# dual_encoder_shield_5v_revb.net
KiCad netlist of a schematic drawn in EAGLE
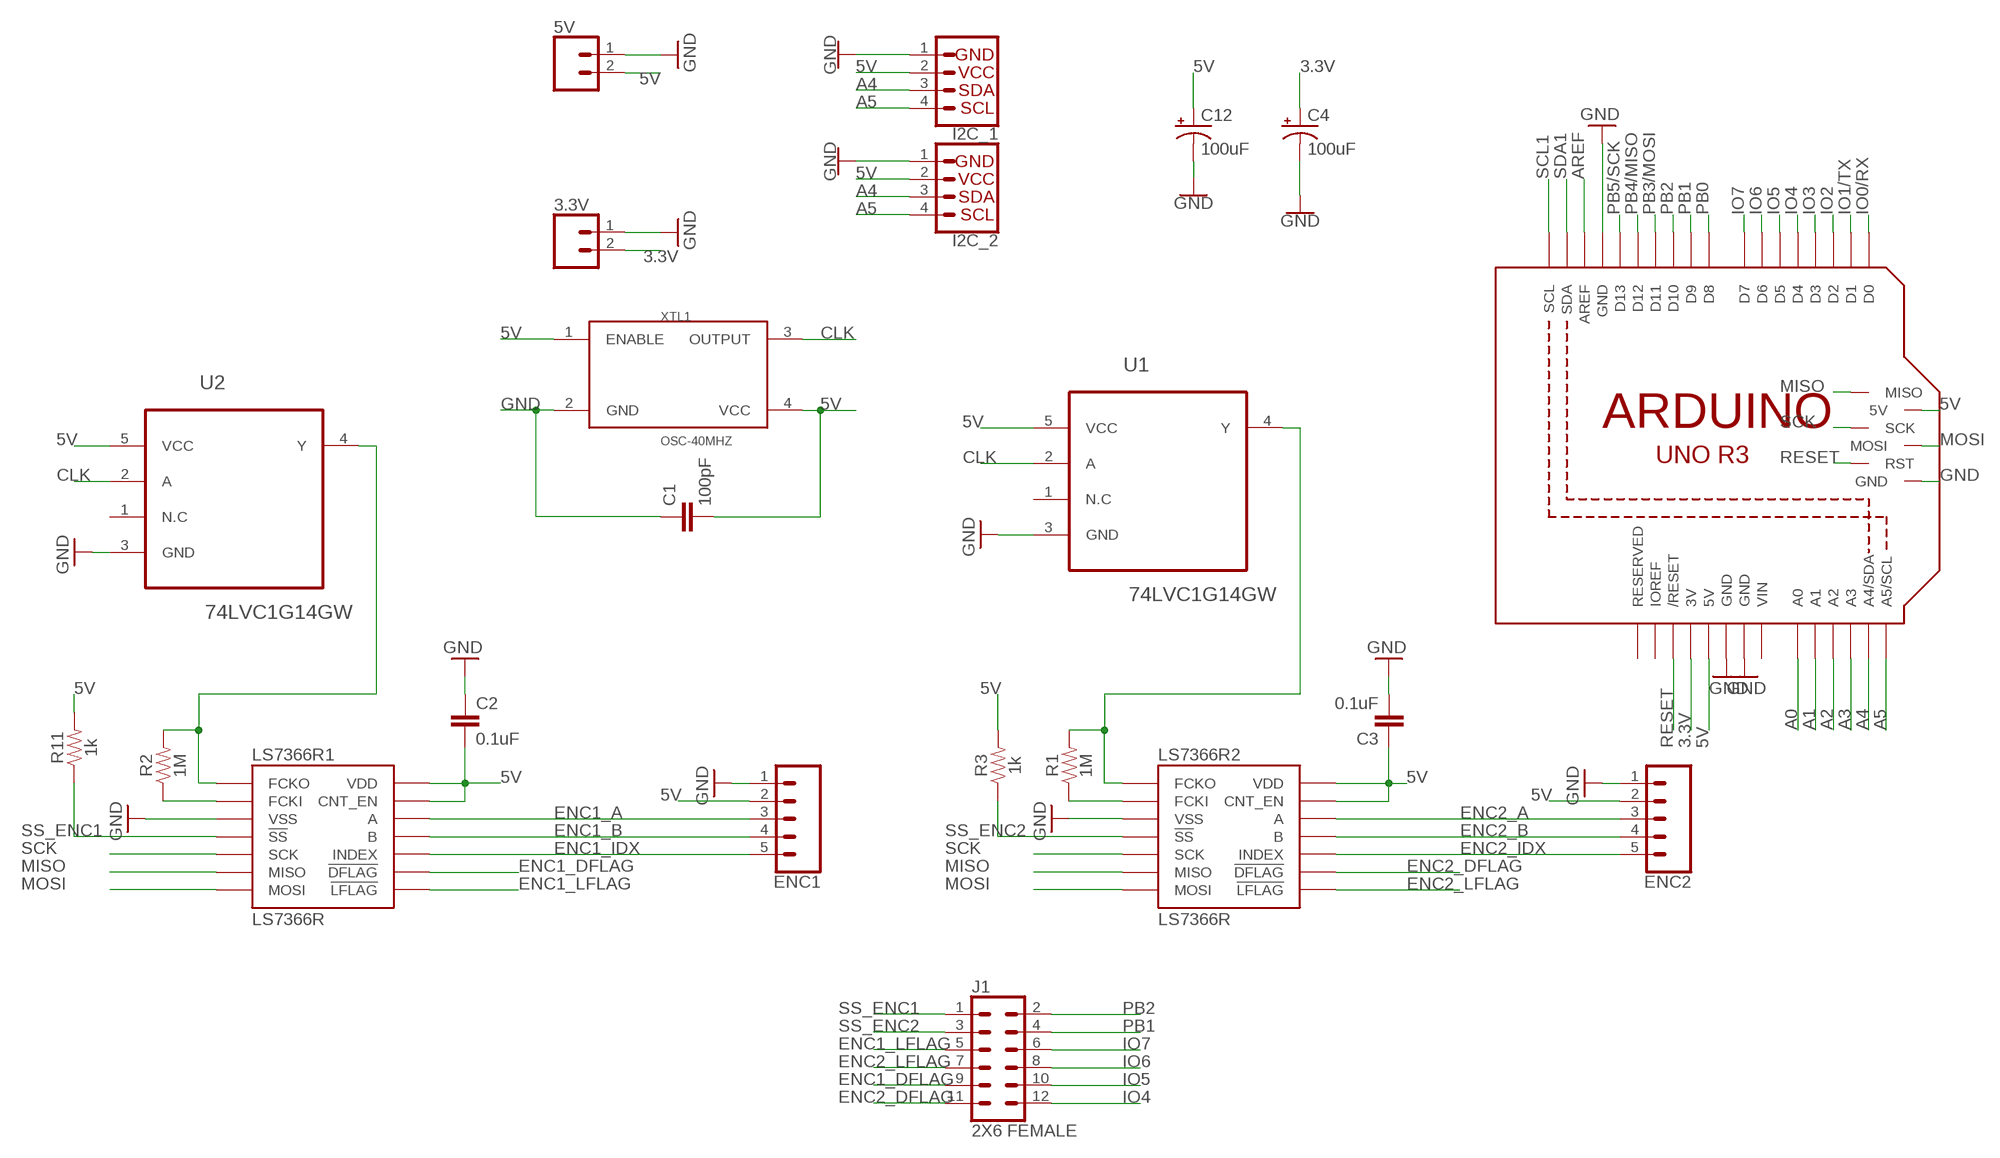
[diagram p0: schematic, sheet 1]

(export (version "E")
  (design (tool "Eeschema 10.0.6"))
  (components
    (comp (ref "3.3V")
      (value "CONN_02-JST-2MM-SMT")
      (footprint "eagle-import:JST-2-SMD")
      (libsource (lib "eagle-import") (part "CONN_02-JST-2MM-SMT"))
    )
    (comp (ref "5V")
      (value "CONN_02-JST-2MM-SMT")
      (footprint "eagle-import:JST-2-SMD")
      (libsource (lib "eagle-import") (part "CONN_02-JST-2MM-SMT"))
    )
    (comp (ref "C1")
      (value "100pF")
      (footprint "eagle-import:0603")
      (libsource (lib "eagle-import") (part "100PF-0603-50V-5%"))
    )
    (comp (ref "C2")
      (value "0.1uF")
      (footprint "eagle-import:0603")
      (libsource (lib "eagle-import") (part "0.1UF-0603-25V-5%"))
    )
    (comp (ref "C3")
      (value "0.1uF")
      (footprint "eagle-import:0603")
      (libsource (lib "eagle-import") (part "0.1UF-0603-25V-5%"))
    )
    (comp (ref "C4")
      (value "100uF")
      (footprint "eagle-import:PANASONIC_D")
      (libsource (lib "eagle-import") (part "100UF-POLAR-25V-20%(ELEC)"))
    )
    (comp (ref "C12")
      (value "100uF")
      (footprint "eagle-import:PANASONIC_D")
      (libsource (lib "eagle-import") (part "100UF-POLAR-25V-20%(ELEC)"))
    )
    (comp (ref "ENC1")
      (value "CONN_05")
      (footprint "eagle-import:1X05")
      (libsource (lib "eagle-import") (part "CONN_05"))
    )
    (comp (ref "ENC2")
      (value "CONN_05")
      (footprint "eagle-import:1X05")
      (libsource (lib "eagle-import") (part "CONN_05"))
    )
    (comp (ref "I2C_1")
      (value "QWIIC_CONNECTORJS-1MM")
      (footprint "eagle-import:JST04_1MM_RA")
      (libsource (lib "eagle-import") (part "QWIIC_CONNECTORJS-1MM"))
    )
    (comp (ref "I2C_2")
      (value "QWIIC_CONNECTORJS-1MM")
      (footprint "eagle-import:JST04_1MM_RA")
      (libsource (lib "eagle-import") (part "QWIIC_CONNECTORJS-1MM"))
    )
    (comp (ref "J1")
      (value "2X6 FEMALE")
      (footprint "eagle-import:2X6")
      (libsource (lib "eagle-import") (part "CONN_06X2PTH_FEMALE"))
    )
    (comp (ref "LS7366R1")
      (value "LS7366R")
      (footprint "eagle-import:SOIC14")
      (fields (field (name "MF") "LSI"))
      (libsource (lib "eagle-import") (part "LS7366R"))
    )
    (comp (ref "LS7366R2")
      (value "LS7366R")
      (footprint "eagle-import:SOIC14")
      (fields (field (name "MF") "LSI"))
      (libsource (lib "eagle-import") (part "LS7366R"))
    )
    (comp (ref "M1")
      (value "ARDUINO_R3_ICSP")
      (footprint "eagle-import:ARDUINOR3_ICSP")
      (libsource (lib "eagle-import") (part "ARDUINO_R3_ICSP"))
    )
    (comp (ref "R1")
      (value "1M")
      (footprint "eagle-import:0603")
      (libsource (lib "eagle-import") (part "1MOHM-0603-1/4W-5%"))
    )
    (comp (ref "R2")
      (value "1M")
      (footprint "eagle-import:0603")
      (libsource (lib "eagle-import") (part "1MOHM-0603-1/4W-5%"))
    )
    (comp (ref "R3")
      (value "1k")
      (footprint "eagle-import:0603")
      (libsource (lib "eagle-import") (part "1KOHM-0603-1/10W-1%"))
    )
    (comp (ref "R11")
      (value "1k")
      (footprint "eagle-import:0603")
      (libsource (lib "eagle-import") (part "1KOHM-0603-1/10W-1%"))
    )
    (comp (ref "U1")
      (value "74LVC1G14GW")
      (footprint "eagle-import:SOT65P210X110-5N")
      (fields (field (name "MF") "NXP Semiconductors"))
      (libsource (lib "eagle-import") (part "74LVC1G14GW"))
    )
    (comp (ref "U2")
      (value "74LVC1G14GW")
      (footprint "eagle-import:SOT65P210X110-5N")
      (fields (field (name "MF") "NXP Semiconductors"))
      (libsource (lib "eagle-import") (part "74LVC1G14GW"))
    )
    (comp (ref "XTL1")
      (value "OSC-40MHZ")
      (footprint "eagle-import:OSC_CB3LV-5I-50M000000")
      (libsource (lib "eagle-import") (part "OSC-40MHZ"))
    )
  )
  (nets
    (net (code "1") (name "/3.3V") (class "Default")
      (node (ref "3.3V") (pin "2") (pinfunction "1_2") (pintype "passive"))
      (node (ref "C4") (pin "+") (pinfunction "+_+") (pintype "passive"))
      (node (ref "M1") (pin "3V") (pinfunction "3V_3V") (pintype "power_in"))
    )
    (net (code "2") (name "/5V") (class "Default")
      (node (ref "5V") (pin "2") (pinfunction "1_2") (pintype "passive"))
      (node (ref "C1") (pin "2") (pinfunction "2_2") (pintype "passive"))
      (node (ref "C12") (pin "+") (pinfunction "+_+") (pintype "passive"))
      (node (ref "C2") (pin "2") (pinfunction "2_2") (pintype "passive"))
      (node (ref "C3") (pin "1") (pinfunction "1_1") (pintype "passive"))
      (node (ref "ENC1") (pin "2") (pinfunction "2_2") (pintype "passive"))
      (node (ref "ENC2") (pin "2") (pinfunction "2_2") (pintype "passive"))
      (node (ref "I2C_1") (pin "2") (pinfunction "2_2") (pintype "power_in"))
      (node (ref "I2C_2") (pin "2") (pinfunction "2_2") (pintype "power_in"))
      (node (ref "LS7366R1") (pin "13") (pinfunction "CNT_EN_13") (pintype "bidirectional"))
      (node (ref "LS7366R1") (pin "14") (pinfunction "VDD_14") (pintype "bidirectional"))
      (node (ref "LS7366R2") (pin "13") (pinfunction "CNT_EN_13") (pintype "bidirectional"))
      (node (ref "LS7366R2") (pin "14") (pinfunction "VDD_14") (pintype "bidirectional"))
      (node (ref "M1") (pin "5V") (pinfunction "5V_5V") (pintype "power_in"))
      (node (ref "M1") (pin "5V_ICSP") (pinfunction "5V_5V_ICSP") (pintype "passive"))
      (node (ref "R11") (pin "2") (pinfunction "2_2") (pintype "passive"))
      (node (ref "R3") (pin "2") (pinfunction "2_2") (pintype "passive"))
      (node (ref "U1") (pin "5") (pinfunction "VCC_5") (pintype "power_in"))
      (node (ref "U2") (pin "5") (pinfunction "VCC_5") (pintype "power_in"))
      (node (ref "XTL1") (pin "1") (pinfunction "ENABLE_1") (pintype "bidirectional"))
      (node (ref "XTL1") (pin "4") (pinfunction "VCC_4") (pintype "bidirectional"))
    )
    (net (code "3") (name "/A0") (class "Default")
      (node (ref "M1") (pin "A0") (pinfunction "A0_A0") (pintype "bidirectional"))
    )
    (net (code "4") (name "/A1") (class "Default")
      (node (ref "M1") (pin "A1") (pinfunction "A1_A1") (pintype "bidirectional"))
    )
    (net (code "5") (name "/A2") (class "Default")
      (node (ref "M1") (pin "A2") (pinfunction "A2_A2") (pintype "bidirectional"))
    )
    (net (code "6") (name "/A3") (class "Default")
      (node (ref "M1") (pin "A3") (pinfunction "A3_A3") (pintype "bidirectional"))
    )
    (net (code "7") (name "/A4") (class "Default")
      (node (ref "I2C_1") (pin "3") (pinfunction "3_3") (pintype "passive"))
      (node (ref "I2C_2") (pin "3") (pinfunction "3_3") (pintype "passive"))
      (node (ref "M1") (pin "A4") (pinfunction "A4/SDA_A4") (pintype "bidirectional"))
    )
    (net (code "8") (name "/A5") (class "Default")
      (node (ref "I2C_1") (pin "4") (pinfunction "4_4") (pintype "passive"))
      (node (ref "I2C_2") (pin "4") (pinfunction "4_4") (pintype "passive"))
      (node (ref "M1") (pin "A5") (pinfunction "A5/SCL_A5") (pintype "bidirectional"))
    )
    (net (code "9") (name "/AREF") (class "Default")
      (node (ref "M1") (pin "AREF") (pinfunction "AREF_AREF") (pintype "bidirectional"))
    )
    (net (code "10") (name "/CLK") (class "Default")
      (node (ref "U1") (pin "2") (pinfunction "A_2") (pintype "input"))
      (node (ref "U2") (pin "2") (pinfunction "A_2") (pintype "input"))
      (node (ref "XTL1") (pin "3") (pinfunction "OUTPUT_3") (pintype "bidirectional"))
    )
    (net (code "11") (name "/ENC1_A") (class "Default")
      (node (ref "ENC1") (pin "3") (pinfunction "3_3") (pintype "passive"))
      (node (ref "LS7366R1") (pin "12") (pinfunction "A_12") (pintype "bidirectional"))
    )
    (net (code "12") (name "/ENC1_B") (class "Default")
      (node (ref "ENC1") (pin "4") (pinfunction "4_4") (pintype "passive"))
      (node (ref "LS7366R1") (pin "11") (pinfunction "B_11") (pintype "bidirectional"))
    )
    (net (code "13") (name "/ENC1_DFLAG") (class "Default")
      (node (ref "J1") (pin "9") (pinfunction "9_9") (pintype "passive"))
      (node (ref "LS7366R1") (pin "9") (pinfunction "~{DFLAG}_9") (pintype "bidirectional"))
    )
    (net (code "14") (name "/ENC1_IDX") (class "Default")
      (node (ref "ENC1") (pin "5") (pinfunction "5_5") (pintype "passive"))
      (node (ref "LS7366R1") (pin "10") (pinfunction "INDEX_10") (pintype "bidirectional"))
    )
    (net (code "15") (name "/ENC1_LFLAG") (class "Default")
      (node (ref "J1") (pin "5") (pinfunction "5_5") (pintype "passive"))
      (node (ref "LS7366R1") (pin "8") (pinfunction "~{LFLAG}_8") (pintype "bidirectional"))
    )
    (net (code "16") (name "/ENC2_A") (class "Default")
      (node (ref "ENC2") (pin "3") (pinfunction "3_3") (pintype "passive"))
      (node (ref "LS7366R2") (pin "12") (pinfunction "A_12") (pintype "bidirectional"))
    )
    (net (code "17") (name "/ENC2_B") (class "Default")
      (node (ref "ENC2") (pin "4") (pinfunction "4_4") (pintype "passive"))
      (node (ref "LS7366R2") (pin "11") (pinfunction "B_11") (pintype "bidirectional"))
    )
    (net (code "18") (name "/ENC2_DFLAG") (class "Default")
      (node (ref "J1") (pin "11") (pinfunction "11_11") (pintype "passive"))
      (node (ref "LS7366R2") (pin "9") (pinfunction "~{DFLAG}_9") (pintype "bidirectional"))
    )
    (net (code "19") (name "/ENC2_IDX") (class "Default")
      (node (ref "ENC2") (pin "5") (pinfunction "5_5") (pintype "passive"))
      (node (ref "LS7366R2") (pin "10") (pinfunction "INDEX_10") (pintype "bidirectional"))
    )
    (net (code "20") (name "/ENC2_LFLAG") (class "Default")
      (node (ref "J1") (pin "7") (pinfunction "7_7") (pintype "passive"))
      (node (ref "LS7366R2") (pin "8") (pinfunction "~{LFLAG}_8") (pintype "bidirectional"))
    )
    (net (code "21") (name "/IO0{slash}RX") (class "Default")
      (node (ref "M1") (pin "D0") (pinfunction "D0_D0") (pintype "bidirectional"))
    )
    (net (code "22") (name "/IO1{slash}TX") (class "Default")
      (node (ref "M1") (pin "D1") (pinfunction "D1_D1") (pintype "bidirectional"))
    )
    (net (code "23") (name "/IO2") (class "Default")
      (node (ref "M1") (pin "D2") (pinfunction "D2_D2") (pintype "bidirectional"))
    )
    (net (code "24") (name "/IO3") (class "Default")
      (node (ref "M1") (pin "D3") (pinfunction "D3_D3") (pintype "bidirectional"))
    )
    (net (code "25") (name "/IO4") (class "Default")
      (node (ref "J1") (pin "12") (pinfunction "12_12") (pintype "passive"))
      (node (ref "M1") (pin "D4") (pinfunction "D4_D4") (pintype "bidirectional"))
    )
    (net (code "26") (name "/IO5") (class "Default")
      (node (ref "J1") (pin "10") (pinfunction "10_10") (pintype "passive"))
      (node (ref "M1") (pin "D5") (pinfunction "D5_D5") (pintype "bidirectional"))
    )
    (net (code "27") (name "/IO6") (class "Default")
      (node (ref "J1") (pin "8") (pinfunction "8_8") (pintype "passive"))
      (node (ref "M1") (pin "D6") (pinfunction "D6_D6") (pintype "bidirectional"))
    )
    (net (code "28") (name "/IO7") (class "Default")
      (node (ref "J1") (pin "6") (pinfunction "6_6") (pintype "passive"))
      (node (ref "M1") (pin "D7") (pinfunction "D7_D7") (pintype "bidirectional"))
    )
    (net (code "29") (name "/MISO") (class "Default")
      (node (ref "LS7366R1") (pin "6") (pinfunction "MISO_6") (pintype "bidirectional"))
      (node (ref "LS7366R2") (pin "6") (pinfunction "MISO_6") (pintype "bidirectional"))
      (node (ref "M1") (pin "MISO") (pinfunction "MISO_MISO") (pintype "passive"))
    )
    (net (code "30") (name "/MOSI") (class "Default")
      (node (ref "LS7366R1") (pin "7") (pinfunction "MOSI_7") (pintype "bidirectional"))
      (node (ref "LS7366R2") (pin "7") (pinfunction "MOSI_7") (pintype "bidirectional"))
      (node (ref "M1") (pin "MOSI") (pinfunction "MOSI_MOSI") (pintype "passive"))
    )
    (net (code "31") (name "/PB0") (class "Default")
      (node (ref "M1") (pin "D8") (pinfunction "D8_D8") (pintype "bidirectional"))
    )
    (net (code "32") (name "/PB1") (class "Default")
      (node (ref "J1") (pin "4") (pinfunction "4_4") (pintype "passive"))
      (node (ref "M1") (pin "D9") (pinfunction "D9_D9") (pintype "bidirectional"))
    )
    (net (code "33") (name "/PB2") (class "Default")
      (node (ref "J1") (pin "2") (pinfunction "2_2") (pintype "passive"))
      (node (ref "M1") (pin "D10") (pinfunction "D10_D10") (pintype "bidirectional"))
    )
    (net (code "34") (name "/PB3{slash}MOSI") (class "Default")
      (node (ref "M1") (pin "D11") (pinfunction "D11_D11") (pintype "bidirectional"))
    )
    (net (code "35") (name "/PB4{slash}MISO") (class "Default")
      (node (ref "M1") (pin "D12") (pinfunction "D12_D12") (pintype "bidirectional"))
    )
    (net (code "36") (name "/PB5{slash}SCK") (class "Default")
      (node (ref "M1") (pin "D13") (pinfunction "D13_D13") (pintype "bidirectional"))
    )
    (net (code "37") (name "/RESET") (class "Default")
      (node (ref "M1") (pin "RESET") (pinfunction "/RESET_RESET") (pintype "bidirectional"))
      (node (ref "M1") (pin "RESET_ICSP") (pinfunction "RST_RESET_ICSP") (pintype "passive"))
    )
    (net (code "38") (name "/SCK") (class "Default")
      (node (ref "LS7366R1") (pin "5") (pinfunction "SCK_5") (pintype "bidirectional"))
      (node (ref "LS7366R2") (pin "5") (pinfunction "SCK_5") (pintype "bidirectional"))
      (node (ref "M1") (pin "SCK") (pinfunction "SCK_SCK") (pintype "passive"))
    )
    (net (code "39") (name "/SCL1") (class "Default")
      (node (ref "M1") (pin "SCL") (pinfunction "SCL_SCL") (pintype "bidirectional"))
    )
    (net (code "40") (name "/SDA1") (class "Default")
      (node (ref "M1") (pin "SDA") (pinfunction "SDA_SDA") (pintype "bidirectional"))
    )
    (net (code "41") (name "/SS_ENC1") (class "Default")
      (node (ref "J1") (pin "1") (pinfunction "1_1") (pintype "passive"))
      (node (ref "LS7366R1") (pin "4") (pinfunction "~{SS}_4") (pintype "bidirectional"))
      (node (ref "R11") (pin "1") (pinfunction "1_1") (pintype "passive"))
    )
    (net (code "42") (name "/SS_ENC2") (class "Default")
      (node (ref "J1") (pin "3") (pinfunction "3_3") (pintype "passive"))
      (node (ref "LS7366R2") (pin "4") (pinfunction "~{SS}_4") (pintype "bidirectional"))
      (node (ref "R3") (pin "1") (pinfunction "1_1") (pintype "passive"))
    )
    (net (code "43") (name "/VIN") (class "Default")
      (node (ref "M1") (pin "VIN") (pinfunction "VIN_VIN") (pintype "power_in"))
    )
    (net (code "44") (name "GND") (class "Default")
      (node (ref "3.3V") (pin "1") (pinfunction "2_1") (pintype "passive"))
      (node (ref "5V") (pin "1") (pinfunction "2_1") (pintype "passive"))
      (node (ref "C1") (pin "1") (pinfunction "1_1") (pintype "passive"))
      (node (ref "C12") (pin "-") (pinfunction "-_-") (pintype "passive"))
      (node (ref "C2") (pin "1") (pinfunction "1_1") (pintype "passive"))
      (node (ref "C3") (pin "2") (pinfunction "2_2") (pintype "passive"))
      (node (ref "C4") (pin "-") (pinfunction "-_-") (pintype "passive"))
      (node (ref "ENC1") (pin "1") (pinfunction "1_1") (pintype "passive"))
      (node (ref "ENC2") (pin "1") (pinfunction "1_1") (pintype "passive"))
      (node (ref "I2C_1") (pin "1") (pinfunction "1_1") (pintype "power_in"))
      (node (ref "I2C_2") (pin "1") (pinfunction "1_1") (pintype "power_in"))
      (node (ref "LS7366R1") (pin "3") (pinfunction "VSS_3") (pintype "bidirectional"))
      (node (ref "LS7366R2") (pin "3") (pinfunction "VSS_3") (pintype "bidirectional"))
      (node (ref "M1") (pin "GND") (pinfunction "GND_GND") (pintype "power_in"))
      (node (ref "M1") (pin "GND@1") (pinfunction "GND_GND@1") (pintype "power_in"))
      (node (ref "M1") (pin "GND@2") (pinfunction "GND_GND@2") (pintype "passive"))
      (node (ref "M1") (pin "GND@3") (pinfunction "GND_GND@3") (pintype "power_in"))
      (node (ref "U1") (pin "3") (pinfunction "GND_3") (pintype "passive"))
      (node (ref "U2") (pin "3") (pinfunction "GND_3") (pintype "passive"))
      (node (ref "XTL1") (pin "2") (pinfunction "GND_2") (pintype "bidirectional"))
    )
    (net (code "45") (name "Net-(LS7366R1-FCKI)") (class "Default")
      (node (ref "LS7366R1") (pin "2") (pinfunction "FCKI_2") (pintype "bidirectional"))
      (node (ref "R2") (pin "1") (pinfunction "1_1") (pintype "passive"))
    )
    (net (code "46") (name "Net-(LS7366R1-FCKO)") (class "Default")
      (node (ref "LS7366R1") (pin "1") (pinfunction "FCKO_1") (pintype "bidirectional"))
      (node (ref "R2") (pin "2") (pinfunction "2_2") (pintype "passive"))
      (node (ref "U2") (pin "4") (pinfunction "Y_4") (pintype "output"))
    )
    (net (code "47") (name "Net-(LS7366R2-FCKI)") (class "Default")
      (node (ref "LS7366R2") (pin "2") (pinfunction "FCKI_2") (pintype "bidirectional"))
      (node (ref "R1") (pin "1") (pinfunction "1_1") (pintype "passive"))
    )
    (net (code "48") (name "Net-(LS7366R2-FCKO)") (class "Default")
      (node (ref "LS7366R2") (pin "1") (pinfunction "FCKO_1") (pintype "bidirectional"))
      (node (ref "R1") (pin "2") (pinfunction "2_2") (pintype "passive"))
      (node (ref "U1") (pin "4") (pinfunction "Y_4") (pintype "output"))
    )
    (net (code "49") (name "unconnected-(M1-PadIOREF)") (class "Default")
      (node (ref "M1") (pin "IOREF") (pinfunction "IOREF_IOREF") (pintype "output"))
    )
    (net (code "50") (name "unconnected-(M1-PadRESERVED)") (class "Default")
      (node (ref "M1") (pin "RESERVED") (pinfunction "RESERVED_RESERVED") (pintype "no_connect"))
    )
    (net (code "51") (name "unconnected-(U1-N.C-Pad1)") (class "Default")
      (node (ref "U1") (pin "1") (pinfunction "N.C_1") (pintype "no_connect"))
    )
    (net (code "52") (name "unconnected-(U2-N.C-Pad1)") (class "Default")
      (node (ref "U2") (pin "1") (pinfunction "N.C_1") (pintype "no_connect"))
    )
  )
)
